# IR-Sensor.net
KiCad netlist of a schematic drawn in Altium Designer
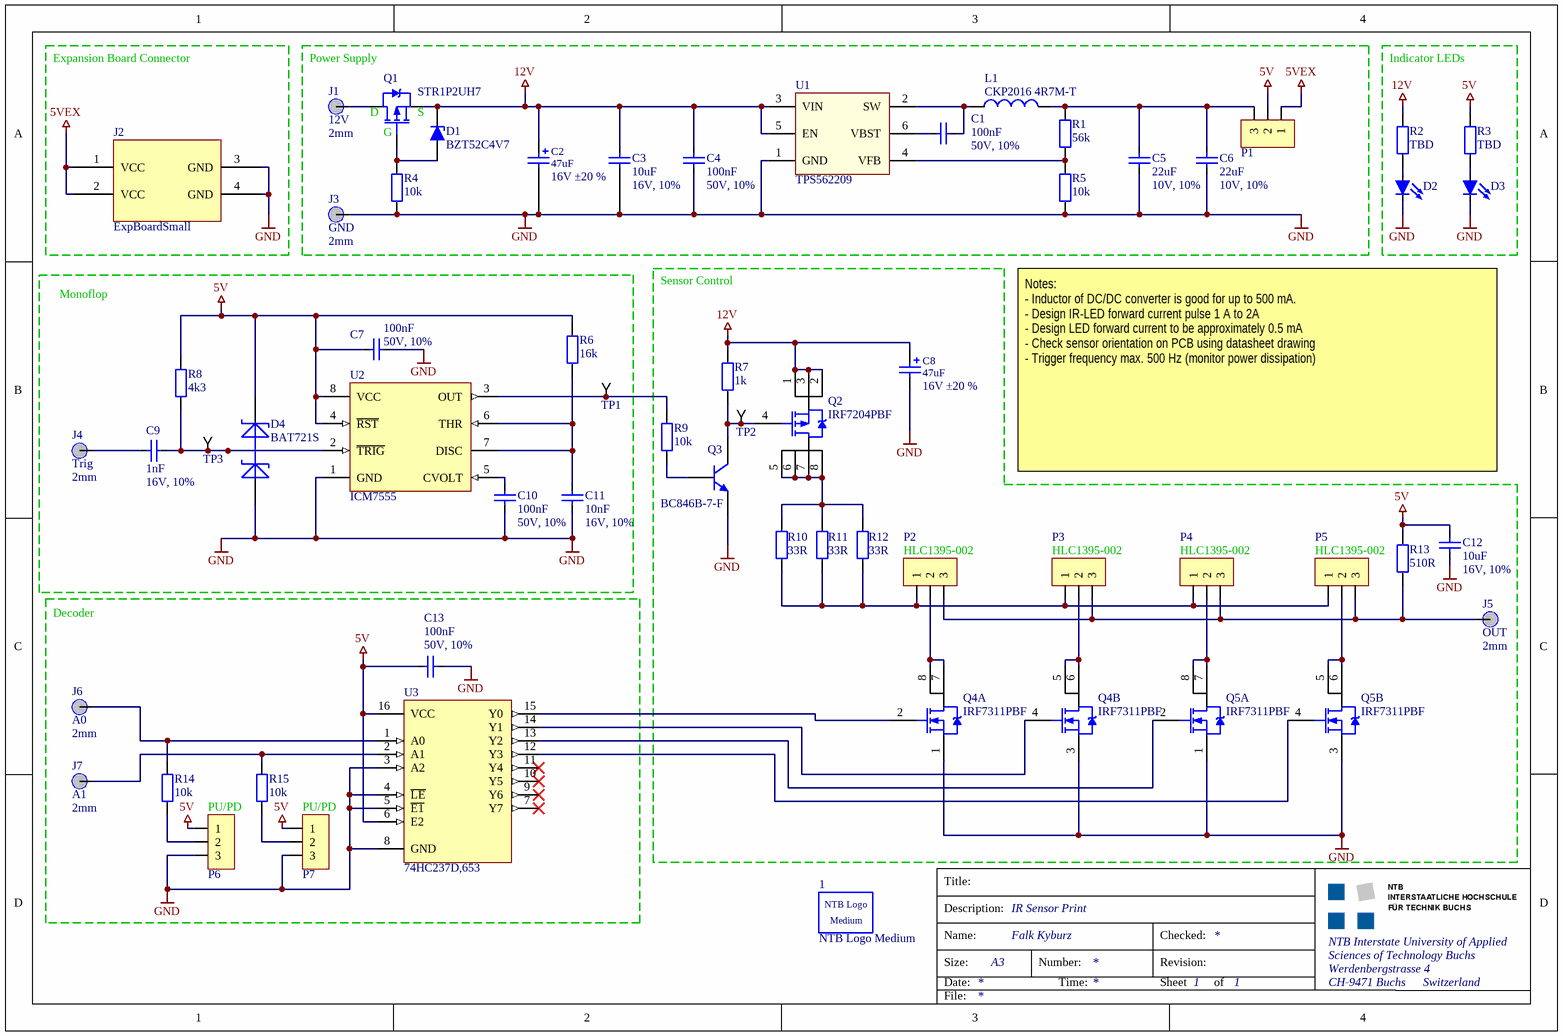
[diagram p0: IR-Sensor.SchDoc]

(export (version "E")
  (design (tool "Eeschema 10.0.6"))
  (components
    (comp (ref "1")
      (value "NTB Logo Medium")
      (footprint "NTB Logo Medium")
      (libsource (lib "IR-Sensor") (part "NTB Logo Medium"))
    )
    (comp (ref "C1")
      (value "100nF")
      (footprint "CAP-0805[2012]")
      (description "100n 50V X7R MLCC 0805 (1608 Metric)")
      (fields (field (name "TOLERANCE") "10%") (field (name "VALADDON") "50V, 10%"))
      (libsource (lib "IR-Sensor") (part "MLCC 0805 100n 50V"))
    )
    (comp (ref "C2")
      (value "47uF")
      (footprint "CDE_CAP AVE CODE D_H")
      (description "ELKO, 47uF, 16V, CDE_AVE476M16D16T-F_AVE CODE D")
      (fields
        (field (name "MANUFACTURER") "Cornell Dubilier")
        (field (name "VALUEADDON") "16V ±20 %")
        (field (name "Comment") "AVE476M16D16T-F")
        (field (name "PUBLISHER") "Stefan Ursella, M.Eng")
      )
      (libsource (lib "IR-Sensor") (part "ELKO 47uF 16V"))
    )
    (comp (ref "C3")
      (value "10uF")
      (footprint "CAP-1206[3216]")
      (description "10u 16V X7R MLCC 1206 (3016 Metric)")
      (fields (field (name "TOLERANCE") "10%") (field (name "VALADDON") "16V, 10%"))
      (libsource (lib "IR-Sensor") (part "MLCC 1206 10u 16V"))
    )
    (comp (ref "C4")
      (value "100nF")
      (footprint "CAP-0805[2012]")
      (description "100n 50V X7R MLCC 0805 (1608 Metric)")
      (fields (field (name "TOLERANCE") "10%") (field (name "VALADDON") "50V, 10%"))
      (libsource (lib "IR-Sensor") (part "MLCC 0805 100n 50V"))
    )
    (comp (ref "C5")
      (value "22uF")
      (footprint "CAP-1206[3216]")
      (description "22u 10V X7R MLCC 1206 (3016 Metric)")
      (fields (field (name "TOLERANCE") "10%") (field (name "VALADDON") "10V, 10%"))
      (libsource (lib "IR-Sensor") (part "MLCC 1206 22u 10V"))
    )
    (comp (ref "C6")
      (value "22uF")
      (footprint "CAP-1206[3216]")
      (description "22u 10V X7R MLCC 1206 (3016 Metric)")
      (fields (field (name "TOLERANCE") "10%") (field (name "VALADDON") "10V, 10%"))
      (libsource (lib "IR-Sensor") (part "MLCC 1206 22u 10V"))
    )
    (comp (ref "C7")
      (value "100nF")
      (footprint "CAP-0805[2012]")
      (description "100n 50V X7R MLCC 0805 (1608 Metric)")
      (fields (field (name "TOLERANCE") "10%") (field (name "VALADDON") "50V, 10%"))
      (libsource (lib "IR-Sensor") (part "MLCC 0805 100n 50V"))
    )
    (comp (ref "C8")
      (value "47uF")
      (footprint "CDE_CAP AVE CODE D_H")
      (description "ELKO, 47uF, 16V, CDE_AVE476M16D16T-F_AVE CODE D")
      (fields
        (field (name "MANUFACTURER") "Cornell Dubilier")
        (field (name "VALUEADDON") "16V ±20 %")
        (field (name "Comment") "AVE476M16D16T-F")
        (field (name "PUBLISHER") "Stefan Ursella, M.Eng")
      )
      (libsource (lib "IR-Sensor") (part "ELKO 47uF 16V"))
    )
    (comp (ref "C9")
      (value "1nF")
      (footprint "CAP-0805[2012]")
      (description "MLCC - SMD/SMT 0805 1000pF 16V C0G 10%")
      (fields
        (field (name "MANUFACTURER") "Vishay")
        (field (name "VALUEADDON") "16V, 10%")
        (field (name "PUBLISHER") "SCLM")
      )
      (libsource (lib "IR-Sensor") (part "MLCC 0805 1n 16V"))
    )
    (comp (ref "C10")
      (value "100nF")
      (footprint "CAP-0805[2012]")
      (description "100n 50V X7R MLCC 0805 (1608 Metric)")
      (fields (field (name "TOLERANCE") "10%") (field (name "VALADDON") "50V, 10%"))
      (libsource (lib "IR-Sensor") (part "MLCC 0805 100n 50V"))
    )
    (comp (ref "C11")
      (value "10nF")
      (footprint "CAP-0805[2012]")
      (description "10n 16V X7R MLCC 0805")
      (fields
        (field (name "MANUFACTURER") "AVX")
        (field (name "VALUEADDON") "16V, 10%")
        (field (name "PUBLISHER") "SCLM")
      )
      (libsource (lib "IR-Sensor") (part "MLCC 0805 10n 16V"))
    )
    (comp (ref "C12")
      (value "10uF")
      (footprint "CAP-1206[3216]")
      (description "10u 16V X7R MLCC 1206 (3016 Metric)")
      (fields (field (name "TOLERANCE") "10%") (field (name "VALADDON") "16V, 10%"))
      (libsource (lib "IR-Sensor") (part "MLCC 1206 10u 16V"))
    )
    (comp (ref "C13")
      (value "100nF")
      (footprint "CAP-0805[2012]")
      (description "100n 50V X7R MLCC 0805 (1608 Metric)")
      (fields (field (name "TOLERANCE") "10%") (field (name "VALADDON") "50V, 10%"))
      (libsource (lib "IR-Sensor") (part "MLCC 0805 100n 50V"))
    )
    (comp (ref "D1")
      (value "BZT52C4V7")
      (footprint "SOD-123")
      (description "4.7V Zener-Diode, BZT52C4V7")
      (libsource (lib "IR-Sensor") (part "BZT52C4V7"))
    )
    (comp (ref "D2")
      (value "LTST-C190GKT")
      (footprint "LED 0603 green")
      (description "LED SMD 0603 green 6mcd")
      (libsource (lib "IR-Sensor") (part "LED Green"))
    )
    (comp (ref "D3")
      (value "LTST-C190GKT")
      (footprint "LED 0603 green")
      (description "LED SMD 0603 green 6mcd")
      (libsource (lib "IR-Sensor") (part "LED Green"))
    )
    (comp (ref "D4")
      (value "BAT721S")
      (footprint "SOT-23")
      (description "NXP  BAT721S  SCHOTTKY-DIODE, 2FACH")
      (fields (field (name "MANUFACTURER") "NXP") (field (name "PUBLISHER") "SCNP"))
      (libsource (lib "IR-Sensor") (part "BAT721S-SOT23"))
    )
    (comp (ref "J1")
      (value "12V")
      (footprint "Laborbuchse 2mm")
      (description "Laborbuchse")
      (fields (field (name "SIZE") "2mm") (field (name "PUBLISHER") "B.Sc. Ursella"))
      (libsource (lib "IR-Sensor") (part "Laborbuchse"))
    )
    (comp (ref "J2")
      (value "ExpBoardSmall")
      (footprint "EXPBOARDCON")
      (libsource (lib "IR-Sensor") (part "ExpBoardSmall"))
    )
    (comp (ref "J3")
      (value "GND")
      (footprint "Laborbuchse 2mm")
      (description "Laborbuchse")
      (fields (field (name "SIZE") "2mm") (field (name "PUBLISHER") "B.Sc. Ursella"))
      (libsource (lib "IR-Sensor") (part "Laborbuchse"))
    )
    (comp (ref "J4")
      (value "Trig")
      (footprint "Laborbuchse 2mm")
      (description "Laborbuchse")
      (fields (field (name "SIZE") "2mm") (field (name "PUBLISHER") "B.Sc. Ursella"))
      (libsource (lib "IR-Sensor") (part "Laborbuchse"))
    )
    (comp (ref "J5")
      (value "OUT")
      (footprint "Laborbuchse 2mm")
      (description "Laborbuchse")
      (fields (field (name "SIZE") "2mm") (field (name "PUBLISHER") "B.Sc. Ursella"))
      (libsource (lib "") (part "Laborbuchse_1"))
    )
    (comp (ref "J6")
      (value "A0")
      (footprint "Laborbuchse 2mm")
      (description "Laborbuchse")
      (fields (field (name "SIZE") "2mm") (field (name "PUBLISHER") "B.Sc. Ursella"))
      (libsource (lib "IR-Sensor") (part "Laborbuchse"))
    )
    (comp (ref "J7")
      (value "A1")
      (footprint "Laborbuchse 2mm")
      (description "Laborbuchse")
      (fields (field (name "SIZE") "2mm") (field (name "PUBLISHER") "B.Sc. Ursella"))
      (libsource (lib "IR-Sensor") (part "Laborbuchse"))
    )
    (comp (ref "L1")
      (value "CKP2016 4R7M-T")
      (footprint "IND-0806")
      (description "MULTILAYER CHIP POWER INDUCTORS")
      (libsource (lib "IR-Sensor") (part "L 4.7u"))
    )
    (comp (ref "P1")
      (value "3 Pin Header")
      (footprint "3PIN HEADER 2.54MM")
      (description "3 Pin Header 2.54mm")
      (fields (field (name "PUBLISHER") "SCLM"))
      (libsource (lib "") (part "3 Pin Header_1"))
    )
    (comp (ref "P2")
      (value "3 Pin Header Buchse")
      (footprint "3PIN HEADER SOCKET 2.54MM")
      (description "3 Pin Header 2.54mm Buchse")
      (libsource (lib "IR-Sensor") (part "3 Pin Header Buchse"))
    )
    (comp (ref "P3")
      (value "3 Pin Header Buchse")
      (footprint "3PIN HEADER SOCKET 2.54MM")
      (description "3 Pin Header 2.54mm Buchse")
      (libsource (lib "IR-Sensor") (part "3 Pin Header Buchse"))
    )
    (comp (ref "P4")
      (value "3 Pin Header Buchse")
      (footprint "3PIN HEADER SOCKET 2.54MM")
      (description "3 Pin Header 2.54mm Buchse")
      (libsource (lib "IR-Sensor") (part "3 Pin Header Buchse"))
    )
    (comp (ref "P5")
      (value "3 Pin Header Buchse")
      (footprint "3PIN HEADER SOCKET 2.54MM")
      (description "3 Pin Header 2.54mm Buchse")
      (libsource (lib "IR-Sensor") (part "3 Pin Header Buchse"))
    )
    (comp (ref "P6")
      (value "3 Pin Header")
      (footprint "3PIN HEADER 2.54MM")
      (description "3 Pin Header 2.54mm")
      (fields (field (name "PUBLISHER") "SCLM"))
      (libsource (lib "IR-Sensor") (part "3 Pin Header"))
    )
    (comp (ref "P7")
      (value "3 Pin Header")
      (footprint "3PIN HEADER 2.54MM")
      (description "3 Pin Header 2.54mm")
      (fields (field (name "PUBLISHER") "SCLM"))
      (libsource (lib "IR-Sensor") (part "3 Pin Header"))
    )
    (comp (ref "Q1")
      (value "STR1P2UH7")
      (footprint "SOT-23")
      (description "Low Power P-Kanal Mosfet")
      (fields (field (name "MANUFACTURER") "ST Microelectronics"))
      (libsource (lib "IR-Sensor") (part "STR1P2UH7"))
    )
    (comp (ref "Q2")
      (value "IRF7204PBF")
      (footprint "SOIC-8")
      (description "High Power P-Kanal Mosfet")
      (fields
        (field (name "MANUFACTURER") "International Rectifiers")
        (field (name "PUBLISHER") "Altium Limited")
      )
      (libsource (lib "IR-Sensor") (part "IRF7204"))
    )
    (comp (ref "Q3")
      (value "BC846B-7-F")
      (footprint "SOT-23")
      (description "NPN General-purpose Transistor")
      (fields (field (name "MANUFACTURER") "DIODES INC") (field (name "PUBLISHER") "Altium Limited"))
      (libsource (lib "IR-Sensor") (part "BC846B-SOT23"))
    )
    (comp (ref "Q4")
      (value "IRF7311PBF")
      (footprint "SOIC-8")
      (description "Dual N-Kanal Mosfet")
      (fields
        (field (name "MANUFACTURER") "International Rectifier")
        (field (name "PUBLISHER") "Altium Limited")
      )
      (libsource (lib "IR-Sensor") (part "IRF7311"))
    )
    (comp (ref "Q5")
      (value "IRF7311PBF")
      (footprint "SOIC-8")
      (description "Dual N-Kanal Mosfet")
      (fields
        (field (name "MANUFACTURER") "International Rectifier")
        (field (name "PUBLISHER") "Altium Limited")
      )
      (libsource (lib "IR-Sensor") (part "IRF7311"))
    )
    (comp (ref "R1")
      (value "56k")
      (footprint "RES-0805[2012]")
      (description "0805 (2013 Metric) 1/10 W 10K 1 Thick Film Chip Resistor")
      (fields (field (name "POWER") "1/10 W") (field (name "TOLERANCE") "1%"))
      (libsource (lib "IR-Sensor") (part "RES 0805"))
    )
    (comp (ref "R2")
      (value "TBD")
      (footprint "RES-0805[2012]")
      (description "0805 (2013 Metric) 1/10 W 10K 1 Thick Film Chip Resistor")
      (fields (field (name "POWER") "1/10 W") (field (name "TOLERANCE") "1%"))
      (libsource (lib "IR-Sensor") (part "RES 0805"))
    )
    (comp (ref "R3")
      (value "TBD")
      (footprint "RES-0805[2012]")
      (description "0805 (2013 Metric) 1/10 W 10K 1 Thick Film Chip Resistor")
      (fields (field (name "POWER") "1/10 W") (field (name "TOLERANCE") "1%"))
      (libsource (lib "IR-Sensor") (part "RES 0805"))
    )
    (comp (ref "R4")
      (value "10k")
      (footprint "RES-0805[2012]")
      (description "0805 (2013 Metric) 1/10 W 10K 1 Thick Film Chip Resistor")
      (fields (field (name "POWER") "1/10 W") (field (name "TOLERANCE") "1%"))
      (libsource (lib "IR-Sensor") (part "RES 0805"))
    )
    (comp (ref "R5")
      (value "10k")
      (footprint "RES-0805[2012]")
      (description "0805 (2013 Metric) 1/10 W 10K 1 Thick Film Chip Resistor")
      (fields (field (name "POWER") "1/10 W") (field (name "TOLERANCE") "1%"))
      (libsource (lib "IR-Sensor") (part "RES 0805"))
    )
    (comp (ref "R6")
      (value "16k")
      (footprint "RES-0805[2012]")
      (description "0805 (2013 Metric) 1/10 W 10K 1 Thick Film Chip Resistor")
      (fields (field (name "POWER") "1/10 W") (field (name "TOLERANCE") "1%"))
      (libsource (lib "IR-Sensor") (part "RES 0805"))
    )
    (comp (ref "R7")
      (value "1k")
      (footprint "RES-0805[2012]")
      (description "0805 (2013 Metric) 1/10 W 10K 1 Thick Film Chip Resistor")
      (fields (field (name "POWER") "1/10 W") (field (name "TOLERANCE") "1%"))
      (libsource (lib "IR-Sensor") (part "RES 0805"))
    )
    (comp (ref "R8")
      (value "4k3")
      (footprint "RES-0805[2012]")
      (description "0805 (2013 Metric) 1/10 W 10K 1 Thick Film Chip Resistor")
      (fields (field (name "POWER") "1/10 W") (field (name "TOLERANCE") "1%"))
      (libsource (lib "IR-Sensor") (part "RES 0805"))
    )
    (comp (ref "R9")
      (value "10k")
      (footprint "RES-0805[2012]")
      (description "0805 (2013 Metric) 1/10 W 10K 1 Thick Film Chip Resistor")
      (fields (field (name "POWER") "1/10 W") (field (name "TOLERANCE") "1%"))
      (libsource (lib "IR-Sensor") (part "RES 0805"))
    )
    (comp (ref "R10")
      (value "33R")
      (footprint "RES-0805[2012]")
      (description "1R8 0.125W 1% 0805 (2012 Metric)  SMD")
      (fields (field (name "Comment") "10R 1% 0805(2012)"))
      (libsource (lib "NTB Vault") (part "PassResBas0805-00750-A.1"))
    )
    (comp (ref "R11")
      (value "33R")
      (footprint "RES-0805[2012]")
      (description "1R8 0.125W 1% 0805 (2012 Metric)  SMD")
      (fields (field (name "Comment") "10R 1% 0805(2012)"))
      (libsource (lib "NTB Vault") (part "PassResBas0805-00750-A.1"))
    )
    (comp (ref "R12")
      (value "33R")
      (footprint "RES-0805[2012]")
      (description "1R8 0.125W 1% 0805 (2012 Metric)  SMD")
      (fields (field (name "Comment") "10R 1% 0805(2012)"))
      (libsource (lib "NTB Vault") (part "PassResBas0805-00750-A.1"))
    )
    (comp (ref "R13")
      (value "510R")
      (footprint "RES-0805[2012]")
      (description "0805 (2013 Metric) 1/10 W 10K 1 Thick Film Chip Resistor")
      (fields (field (name "POWER") "1/10 W") (field (name "TOLERANCE") "1%"))
      (libsource (lib "IR-Sensor") (part "RES 0805"))
    )
    (comp (ref "R14")
      (value "10k")
      (footprint "RES-0805[2012]")
      (description "0805 (2013 Metric) 1/10 W 10K 1 Thick Film Chip Resistor")
      (fields (field (name "POWER") "1/10 W") (field (name "TOLERANCE") "1%"))
      (libsource (lib "IR-Sensor") (part "RES 0805"))
    )
    (comp (ref "R15")
      (value "10k")
      (footprint "RES-0805[2012]")
      (description "0805 (2013 Metric) 1/10 W 10K 1 Thick Film Chip Resistor")
      (fields (field (name "POWER") "1/10 W") (field (name "TOLERANCE") "1%"))
      (libsource (lib "IR-Sensor") (part "RES 0805"))
    )
    (comp (ref "TP1")
      (value "Testpoint SMD 1206")
      (footprint "TP-SMD-1206")
      (description "Testpoint xSmall")
      (libsource (lib "IR-Sensor") (part "Testpoint SMD 1206"))
    )
    (comp (ref "TP2")
      (value "Testpoint SMD 1206")
      (footprint "TP-SMD-1206")
      (description "Testpoint xSmall")
      (libsource (lib "altium-import") (part "root_0_Testpoint SMD 1206_"))
    )
    (comp (ref "TP3")
      (value "Testpoint SMD 1206")
      (footprint "TP-SMD-1206")
      (description "Testpoint xSmall")
      (libsource (lib "IR-Sensor") (part "Testpoint SMD 1206"))
    )
    (comp (ref "U1")
      (value "TPS562209")
      (footprint "SOT-23-6")
      (description "3-A Synchronous Step-Down Voltage Regulator")
      (libsource (lib "IR-Sensor") (part "TPS562209-SOT23-6"))
    )
    (comp (ref "U2")
      (value "ICM7555")
      (footprint "SOIC-8")
      (description "General purpose CMOS timer")
      (fields
        (field (name "MANUFACTURER") "National Semiconductor")
        (field (name "PUBLISHER") "Altium Hobart Technology Centre")
      )
      (libsource (lib "IR-Sensor") (part "ICM7555-SOIC8"))
    )
    (comp (ref "U3")
      (value "74HC237D,653")
      (footprint "SOIC-16")
      (description "3-to-8 line decoder, demultiplexer, NXP, SO16")
      (fields (field (name "MANUFACTURER") "NXP") (field (name "PUBLISHER") "SCLM"))
      (libsource (lib "IR-Sensor") (part "74HC237D-SOIC16"))
    )
  )
  (nets
    (net (code "1") (name "5V") (class "Default")
      (node (ref "C12") (pin "1") (pinfunction "Pos_1") (pintype "passive"))
      (node (ref "C13") (pin "1") (pinfunction "Pos_1") (pintype "passive"))
      (node (ref "C7") (pin "1") (pinfunction "Pos_1") (pintype "passive"))
      (node (ref "D4") (pin "2") (pinfunction "cathode2_2") (pintype "passive"))
      (node (ref "P1") (pin "2") (pinfunction "2_2") (pintype "passive"))
      (node (ref "P6") (pin "1") (pinfunction "1_1") (pintype "passive"))
      (node (ref "P7") (pin "1") (pinfunction "1_1") (pintype "passive"))
      (node (ref "R13") (pin "2") (pinfunction "2_2") (pintype "passive"))
      (node (ref "R3") (pin "2") (pinfunction "2_2") (pintype "passive"))
      (node (ref "R6") (pin "2") (pinfunction "2_2") (pintype "passive"))
      (node (ref "R8") (pin "2") (pinfunction "2_2") (pintype "passive"))
      (node (ref "U2") (pin "4") (pinfunction "~{RST}_4") (pintype "input"))
      (node (ref "U2") (pin "8") (pinfunction "VCC_8") (pintype "power_in"))
      (node (ref "U3") (pin "16") (pinfunction "VCC_16") (pintype "power_in"))
      (node (ref "U3") (pin "6") (pinfunction "E2_6") (pintype "input"))
    )
    (net (code "2") (name "5VEX") (class "Default")
      (node (ref "J2") (pin "1") (pinfunction "VCC_1") (pintype "passive"))
      (node (ref "J2") (pin "2") (pinfunction "VCC_2") (pintype "passive"))
      (node (ref "P1") (pin "1") (pinfunction "1_1") (pintype "passive"))
    )
    (net (code "3") (name "12V") (class "Default")
      (node (ref "C2") (pin "1") (pinfunction "Pos_1") (pintype "passive"))
      (node (ref "C3") (pin "1") (pinfunction "Pos_1") (pintype "passive"))
      (node (ref "C4") (pin "1") (pinfunction "Pos_1") (pintype "passive"))
      (node (ref "C8") (pin "1") (pinfunction "Pos_1") (pintype "passive"))
      (node (ref "D1") (pin "1") (pinfunction "K_1") (pintype "passive"))
      (node (ref "Q1") (pin "2") (pinfunction "S_2") (pintype "passive"))
      (node (ref "Q2") (pin "1") (pinfunction "S_1") (pintype "passive"))
      (node (ref "Q2") (pin "2") (pinfunction "S_2") (pintype "passive"))
      (node (ref "Q2") (pin "3") (pinfunction "S_3") (pintype "passive"))
      (node (ref "R2") (pin "2") (pinfunction "2_2") (pintype "passive"))
      (node (ref "R7") (pin "2") (pinfunction "2_2") (pintype "passive"))
      (node (ref "U1") (pin "3") (pinfunction "VIN_3") (pintype "passive"))
      (node (ref "U1") (pin "5") (pinfunction "EN_5") (pintype "passive"))
    )
    (net (code "4") (name "GND") (class "Default")
      (node (ref "C10") (pin "2") (pinfunction "Neg_2") (pintype "passive"))
      (node (ref "C11") (pin "2") (pinfunction "Neg_2") (pintype "passive"))
      (node (ref "C12") (pin "2") (pinfunction "Neg_2") (pintype "passive"))
      (node (ref "C13") (pin "2") (pinfunction "Neg_2") (pintype "passive"))
      (node (ref "C2") (pin "2") (pinfunction "Neg_2") (pintype "passive"))
      (node (ref "C3") (pin "2") (pinfunction "Neg_2") (pintype "passive"))
      (node (ref "C4") (pin "2") (pinfunction "Neg_2") (pintype "passive"))
      (node (ref "C5") (pin "2") (pinfunction "Neg_2") (pintype "passive"))
      (node (ref "C6") (pin "2") (pinfunction "Neg_2") (pintype "passive"))
      (node (ref "C7") (pin "2") (pinfunction "Neg_2") (pintype "passive"))
      (node (ref "C8") (pin "2") (pinfunction "Neg_2") (pintype "passive"))
      (node (ref "D2") (pin "1") (pinfunction "K_1") (pintype "passive"))
      (node (ref "D3") (pin "1") (pinfunction "K_1") (pintype "passive"))
      (node (ref "D4") (pin "1") (pinfunction "Anode1_1") (pintype "passive"))
      (node (ref "J2") (pin "3") (pinfunction "GND_3") (pintype "passive"))
      (node (ref "J2") (pin "4") (pinfunction "GND_4") (pintype "passive"))
      (node (ref "J3") (pin "1") (pinfunction "1_1") (pintype "passive"))
      (node (ref "P6") (pin "3") (pinfunction "3_3") (pintype "passive"))
      (node (ref "P7") (pin "3") (pinfunction "3_3") (pintype "passive"))
      (node (ref "Q3") (pin "2") (pinfunction "E_2") (pintype "passive"))
      (node (ref "Q4") (pin "1") (pinfunction "S_1") (pintype "passive"))
      (node (ref "Q4") (pin "3") (pinfunction "S_3") (pintype "passive"))
      (node (ref "Q5") (pin "1") (pinfunction "S_1") (pintype "passive"))
      (node (ref "Q5") (pin "3") (pinfunction "S_3") (pintype "passive"))
      (node (ref "R4") (pin "1") (pinfunction "1_1") (pintype "passive"))
      (node (ref "R5") (pin "1") (pinfunction "1_1") (pintype "passive"))
      (node (ref "U1") (pin "1") (pinfunction "GND_1") (pintype "passive"))
      (node (ref "U2") (pin "1") (pinfunction "GND_1") (pintype "power_in"))
      (node (ref "U3") (pin "3") (pinfunction "A2_3") (pintype "input"))
      (node (ref "U3") (pin "4") (pinfunction "LE_4") (pintype "input"))
      (node (ref "U3") (pin "5") (pinfunction "E1_5") (pintype "input"))
      (node (ref "U3") (pin "8") (pinfunction "GND_8") (pintype "power_in"))
    )
    (net (code "5") (name "Net-(C1-Neg)") (class "Default")
      (node (ref "C1") (pin "2") (pinfunction "Neg_2") (pintype "passive"))
      (node (ref "L1") (pin "1") (pinfunction "1_1") (pintype "passive"))
      (node (ref "U1") (pin "2") (pinfunction "SW_2") (pintype "passive"))
    )
    (net (code "6") (name "Net-(C1-Pos)") (class "Default")
      (node (ref "C1") (pin "1") (pinfunction "Pos_1") (pintype "passive"))
      (node (ref "U1") (pin "6") (pinfunction "VBST_6") (pintype "passive"))
    )
    (net (code "7") (name "Net-(C5-Pos)") (class "Default")
      (node (ref "C5") (pin "1") (pinfunction "Pos_1") (pintype "passive"))
      (node (ref "C6") (pin "1") (pinfunction "Pos_1") (pintype "passive"))
      (node (ref "L1") (pin "2") (pinfunction "2_2") (pintype "passive"))
      (node (ref "P1") (pin "3") (pinfunction "3_3") (pintype "passive"))
      (node (ref "R1") (pin "2") (pinfunction "2_2") (pintype "passive"))
    )
    (net (code "8") (name "Net-(C9-Neg)") (class "Default")
      (node (ref "C9") (pin "2") (pinfunction "Neg_2") (pintype "passive"))
      (node (ref "D4") (pin "3") (pinfunction "Cathode1,_anode2_3") (pintype "passive"))
      (node (ref "R8") (pin "1") (pinfunction "1_1") (pintype "passive"))
      (node (ref "TP3") (pin "1") (pinfunction "0_1") (pintype "passive"))
      (node (ref "U2") (pin "2") (pinfunction "TRIG_2") (pintype "input"))
    )
    (net (code "9") (name "Net-(C9-Pos)") (class "Default")
      (node (ref "C9") (pin "1") (pinfunction "Pos_1") (pintype "passive"))
      (node (ref "J4") (pin "1") (pinfunction "1_1") (pintype "passive"))
    )
    (net (code "10") (name "Net-(C10-Pos)") (class "Default")
      (node (ref "C10") (pin "1") (pinfunction "Pos_1") (pintype "passive"))
      (node (ref "U2") (pin "5") (pinfunction "CVOLT_5") (pintype "input"))
    )
    (net (code "11") (name "Net-(C11-Pos)") (class "Default")
      (node (ref "C11") (pin "1") (pinfunction "Pos_1") (pintype "passive"))
      (node (ref "R6") (pin "1") (pinfunction "1_1") (pintype "passive"))
      (node (ref "U2") (pin "6") (pinfunction "THR_6") (pintype "input"))
      (node (ref "U2") (pin "7") (pinfunction "DISC_7") (pintype "open_collector"))
    )
    (net (code "12") (name "Net-(D1-A)") (class "Default")
      (node (ref "D1") (pin "2") (pinfunction "A_2") (pintype "passive"))
      (node (ref "Q1") (pin "1") (pinfunction "G_1") (pintype "passive"))
      (node (ref "R4") (pin "2") (pinfunction "2_2") (pintype "passive"))
    )
    (net (code "13") (name "Net-(D2-A)") (class "Default")
      (node (ref "D2") (pin "2") (pinfunction "A_2") (pintype "passive"))
      (node (ref "R2") (pin "1") (pinfunction "1_1") (pintype "passive"))
    )
    (net (code "14") (name "Net-(D3-A)") (class "Default")
      (node (ref "D3") (pin "2") (pinfunction "A_2") (pintype "passive"))
      (node (ref "R3") (pin "1") (pinfunction "1_1") (pintype "passive"))
    )
    (net (code "15") (name "Net-(J5-Pad1)") (class "Default")
      (node (ref "J5") (pin "1") (pinfunction "1_1") (pintype "passive"))
      (node (ref "P2") (pin "3") (pinfunction "3_3") (pintype "passive"))
      (node (ref "P3") (pin "3") (pinfunction "3_3") (pintype "passive"))
      (node (ref "P4") (pin "3") (pinfunction "3_3") (pintype "passive"))
      (node (ref "P5") (pin "3") (pinfunction "3_3") (pintype "passive"))
      (node (ref "R13") (pin "1") (pinfunction "1_1") (pintype "passive"))
    )
    (net (code "16") (name "Net-(P2-Pad1)") (class "Default")
      (node (ref "P2") (pin "1") (pinfunction "1_1") (pintype "passive"))
      (node (ref "P3") (pin "1") (pinfunction "1_1") (pintype "passive"))
      (node (ref "P4") (pin "1") (pinfunction "1_1") (pintype "passive"))
      (node (ref "P5") (pin "1") (pinfunction "1_1") (pintype "passive"))
      (node (ref "R10") (pin "2") (pinfunction "2_2") (pintype "passive"))
      (node (ref "R11") (pin "2") (pinfunction "2_2") (pintype "passive"))
      (node (ref "R12") (pin "2") (pinfunction "2_2") (pintype "passive"))
    )
    (net (code "17") (name "Net-(P2-Pad2)") (class "Default")
      (node (ref "P2") (pin "2") (pinfunction "2_2") (pintype "passive"))
      (node (ref "Q4") (pin "7") (pinfunction "D_7") (pintype "passive"))
      (node (ref "Q4") (pin "8") (pinfunction "D_8") (pintype "passive"))
    )
    (net (code "18") (name "Net-(P3-Pad2)") (class "Default")
      (node (ref "P3") (pin "2") (pinfunction "2_2") (pintype "passive"))
      (node (ref "Q4") (pin "5") (pinfunction "D_5") (pintype "passive"))
      (node (ref "Q4") (pin "6") (pinfunction "D_6") (pintype "passive"))
    )
    (net (code "19") (name "Net-(P4-Pad2)") (class "Default")
      (node (ref "P4") (pin "2") (pinfunction "2_2") (pintype "passive"))
      (node (ref "Q5") (pin "7") (pinfunction "D_7") (pintype "passive"))
      (node (ref "Q5") (pin "8") (pinfunction "D_8") (pintype "passive"))
    )
    (net (code "20") (name "Net-(P5-Pad2)") (class "Default")
      (node (ref "P5") (pin "2") (pinfunction "2_2") (pintype "passive"))
      (node (ref "Q5") (pin "5") (pinfunction "D_5") (pintype "passive"))
      (node (ref "Q5") (pin "6") (pinfunction "D_6") (pintype "passive"))
    )
    (net (code "21") (name "Net-(P6-Pad2)") (class "Default")
      (node (ref "P6") (pin "2") (pinfunction "2_2") (pintype "passive"))
      (node (ref "R14") (pin "1") (pinfunction "1_1") (pintype "passive"))
    )
    (net (code "22") (name "Net-(P7-Pad2)") (class "Default")
      (node (ref "P7") (pin "2") (pinfunction "2_2") (pintype "passive"))
      (node (ref "R15") (pin "1") (pinfunction "1_1") (pintype "passive"))
    )
    (net (code "23") (name "Net-(Q1-D)") (class "Default")
      (node (ref "J1") (pin "1") (pinfunction "1_1") (pintype "passive"))
      (node (ref "Q1") (pin "3") (pinfunction "D_3") (pintype "passive"))
    )
    (net (code "24") (name "Net-(Q2-D-Pad5)") (class "Default")
      (node (ref "Q2") (pin "5") (pinfunction "D_5") (pintype "passive"))
      (node (ref "Q2") (pin "6") (pinfunction "D_6") (pintype "passive"))
      (node (ref "Q2") (pin "7") (pinfunction "D_7") (pintype "passive"))
      (node (ref "Q2") (pin "8") (pinfunction "D_8") (pintype "passive"))
      (node (ref "R10") (pin "1") (pinfunction "1_1") (pintype "passive"))
      (node (ref "R11") (pin "1") (pinfunction "1_1") (pintype "passive"))
      (node (ref "R12") (pin "1") (pinfunction "1_1") (pintype "passive"))
    )
    (net (code "25") (name "Net-(Q2-G)") (class "Default")
      (node (ref "Q2") (pin "4") (pinfunction "G_4") (pintype "passive"))
      (node (ref "Q3") (pin "3") (pinfunction "C_3") (pintype "passive"))
      (node (ref "R7") (pin "1") (pinfunction "1_1") (pintype "passive"))
      (node (ref "TP2") (pin "1") (pinfunction "0_1") (pintype "passive"))
    )
    (net (code "26") (name "Net-(Q3-B)") (class "Default")
      (node (ref "Q3") (pin "1") (pinfunction "B_1") (pintype "passive"))
      (node (ref "R9") (pin "2") (pinfunction "2_2") (pintype "passive"))
    )
    (net (code "27") (name "Net-(Q4A-G)") (class "Default")
      (node (ref "Q4") (pin "2") (pinfunction "G_2") (pintype "passive"))
      (node (ref "U3") (pin "15") (pinfunction "Y0_15") (pintype "output"))
    )
    (net (code "28") (name "Net-(Q4B-G)") (class "Default")
      (node (ref "Q4") (pin "4") (pinfunction "G_4") (pintype "passive"))
      (node (ref "U3") (pin "14") (pinfunction "Y1_14") (pintype "output"))
    )
    (net (code "29") (name "Net-(Q5A-G)") (class "Default")
      (node (ref "Q5") (pin "2") (pinfunction "G_2") (pintype "passive"))
      (node (ref "U3") (pin "13") (pinfunction "Y2_13") (pintype "output"))
    )
    (net (code "30") (name "Net-(Q5B-G)") (class "Default")
      (node (ref "Q5") (pin "4") (pinfunction "G_4") (pintype "passive"))
      (node (ref "U3") (pin "12") (pinfunction "Y3_12") (pintype "output"))
    )
    (net (code "31") (name "Net-(TP1-0)") (class "Default")
      (node (ref "R9") (pin "1") (pinfunction "1_1") (pintype "passive"))
      (node (ref "TP1") (pin "1") (pinfunction "0_1") (pintype "passive"))
      (node (ref "U2") (pin "3") (pinfunction "OUT_3") (pintype "output"))
    )
    (net (code "32") (name "Net-(U1-VFB)") (class "Default")
      (node (ref "R1") (pin "1") (pinfunction "1_1") (pintype "passive"))
      (node (ref "R5") (pin "2") (pinfunction "2_2") (pintype "passive"))
      (node (ref "U1") (pin "4") (pinfunction "VFB_4") (pintype "passive"))
    )
    (net (code "33") (name "Net-(U3-A0)") (class "Default")
      (node (ref "J6") (pin "1") (pinfunction "1_1") (pintype "passive"))
      (node (ref "R14") (pin "2") (pinfunction "2_2") (pintype "passive"))
      (node (ref "U3") (pin "1") (pinfunction "A0_1") (pintype "input"))
    )
    (net (code "34") (name "Net-(U3-A1)") (class "Default")
      (node (ref "J7") (pin "1") (pinfunction "1_1") (pintype "passive"))
      (node (ref "R15") (pin "2") (pinfunction "2_2") (pintype "passive"))
      (node (ref "U3") (pin "2") (pinfunction "A1_2") (pintype "input"))
    )
    (net (code "35") (name "unconnected-(U3-Y4-Pad11)") (class "Default")
      (node (ref "U3") (pin "11") (pinfunction "Y4_11") (pintype "output+no_connect"))
    )
    (net (code "36") (name "unconnected-(U3-Y5-Pad10)") (class "Default")
      (node (ref "U3") (pin "10") (pinfunction "Y5_10") (pintype "output+no_connect"))
    )
    (net (code "37") (name "unconnected-(U3-Y6-Pad9)") (class "Default")
      (node (ref "U3") (pin "9") (pinfunction "Y6_9") (pintype "output+no_connect"))
    )
    (net (code "38") (name "unconnected-(U3-Y7-Pad7)") (class "Default")
      (node (ref "U3") (pin "7") (pinfunction "Y7_7") (pintype "output+no_connect"))
    )
  )
)
